# CAN.net
KiCad netlist of a schematic drawn in Altium Designer
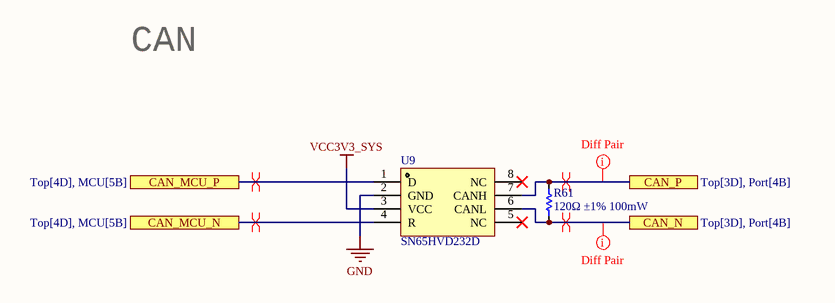
[diagram p0: CAN.SchDoc]

(export (version "E")
  (design (tool "Eeschema 10.0.6"))
  (components
    (comp (ref "R61")
      (value "120Ω ±1% 100mW")
      (footprint "R0603")
      (description "Resistor")
      (fields (field (name "PUBLISHER") "Altium Limited"))
      (libsource (lib "Component") (part "Res"))
    )
    (comp (ref "U9")
      (value "SN65HVD232D")
      (footprint "SOIC127P600X175-8N")
      (fields (field (name "MANUFACTURER") "Texas Instruments"))
      (libsource (lib "IC") (part "SN65HVD232D"))
    )
  )
  (nets
    (net (code "1") (name "/CAN_MCU_N") (class "Default")
      (node (ref "U9") (pin "4") (pinfunction "R_4") (pintype "passive"))
    )
    (net (code "2") (name "/CAN_MCU_P") (class "Default")
      (node (ref "U9") (pin "1") (pinfunction "D_1") (pintype "passive"))
    )
    (net (code "3") (name "/CAN_N") (class "Default")
      (node (ref "R61") (pin "1") (pinfunction "1_1") (pintype "passive"))
      (node (ref "U9") (pin "6") (pinfunction "CANL_6") (pintype "passive"))
    )
    (net (code "4") (name "/CAN_P") (class "Default")
      (node (ref "R61") (pin "2") (pinfunction "2_2") (pintype "passive"))
      (node (ref "U9") (pin "7") (pinfunction "CANH_7") (pintype "passive"))
    )
    (net (code "5") (name "GND") (class "Default")
      (node (ref "U9") (pin "2") (pinfunction "GND_2") (pintype "passive"))
    )
    (net (code "6") (name "VCC3V3_SYS") (class "Default")
      (node (ref "U9") (pin "3") (pinfunction "VCC_3") (pintype "passive"))
    )
    (net (code "7") (name "unconnected-(U9-NC-Pad5)") (class "Default")
      (node (ref "U9") (pin "5") (pinfunction "NC_5") (pintype "passive+no_connect"))
    )
    (net (code "8") (name "unconnected-(U9-NC-Pad8)") (class "Default")
      (node (ref "U9") (pin "8") (pinfunction "NC_8") (pintype "passive+no_connect"))
    )
  )
)
